# DCDC-TPS54361QDPRRQ1.net
KiCad netlist of a schematic drawn in Altium Designer
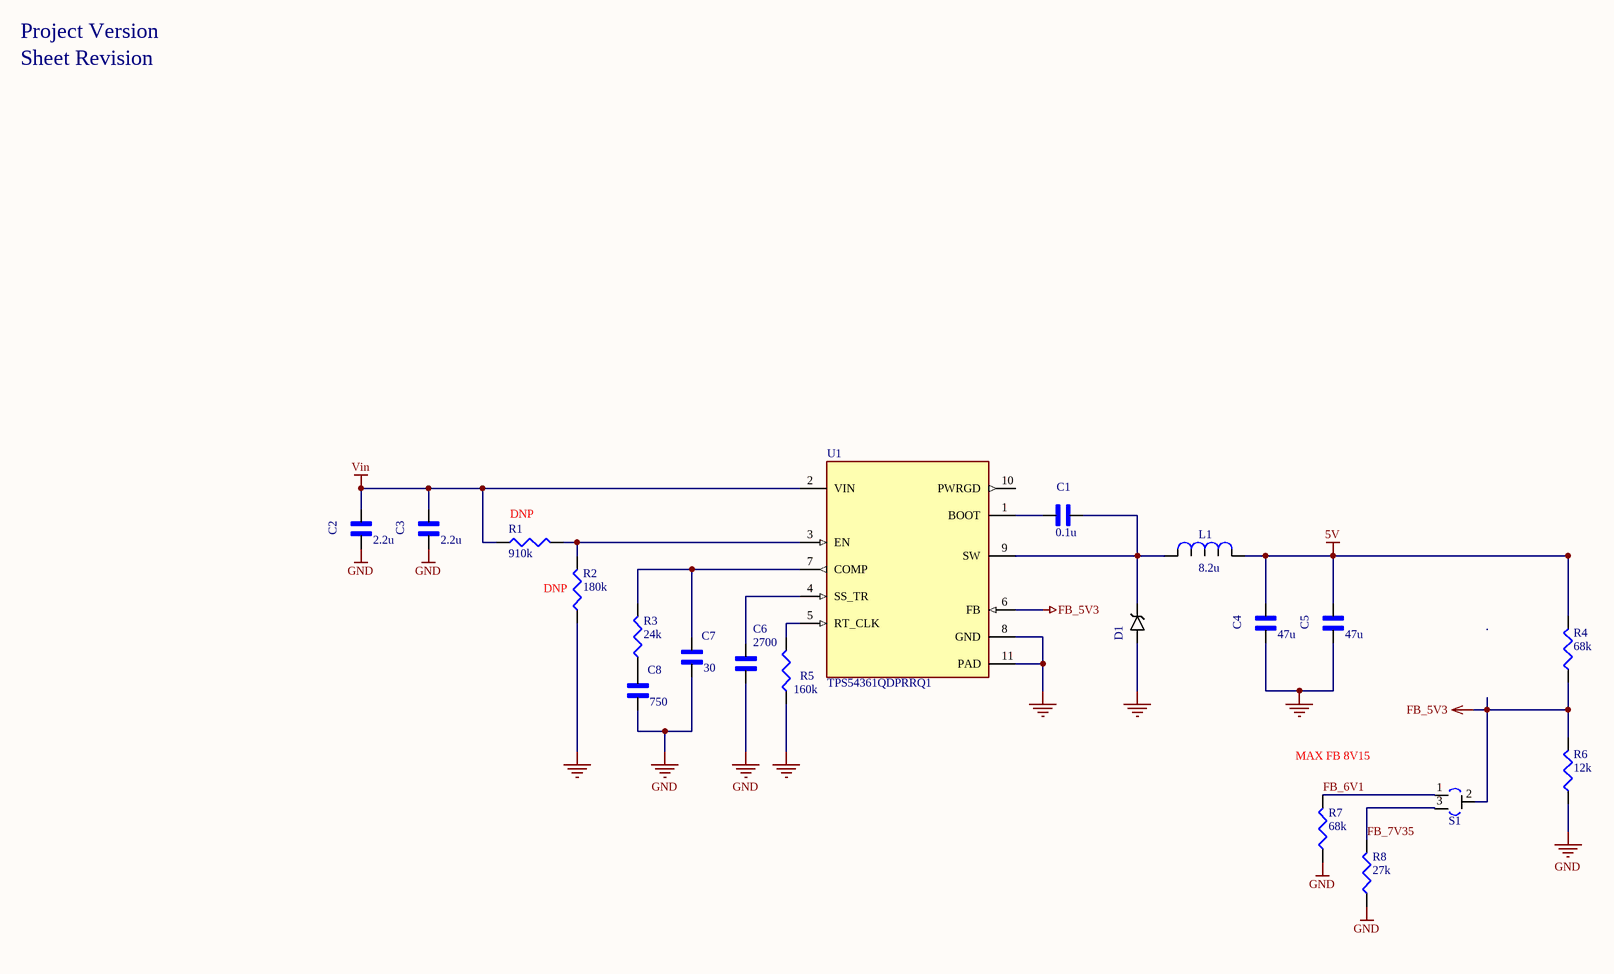
[diagram p0: DCDC-TPS54361QDPRRQ1.SchDoc]

(export (version "E")
  (design (tool "Eeschema 10.0.6"))
  (components
    (comp (ref "C1")
      (value "0.1u")
      (footprint "*CAPC1608X90")
      (description "Cap Thin Film 0.1uf 50v 0603")
      (fields (field (name "MF") "AVX") (field (name "MP") "GX035C104MAT2-500"))
      (libsource (lib "lib") (part "GX035C104MAT2-500"))
    )
    (comp (ref "C2")
      (value "2.2u")
      (footprint "*CAP3216X125N")
      (description "1206 2.2 uF 50 V В±10% Tolerance X7R SMT Multilayer Ceramic Capacitor")
      (fields (field (name "MF") "Murata Electronics") (field (name "MP") "GRM31CR71H225KA88L"))
      (libsource (lib "lib") (part "GRM31CR71H225KA88L"))
    )
    (comp (ref "C3")
      (value "2.2u")
      (footprint "*CAP3216X125N")
      (description "1206 2.2 uF 50 V В±10% Tolerance X7R SMT Multilayer Ceramic Capacitor")
      (fields (field (name "MF") "Murata Electronics") (field (name "MP") "GRM31CR71H225KA88L"))
      (libsource (lib "lib") (part "GRM31CR71H225KA88L"))
    )
    (comp (ref "C4")
      (value "47u")
      (footprint "*CAPC3216X125N")
      (description "Multilayer Ceramic Capacitor, GRM Series, 47 - F, - 10%, X5R, 10 V, 1206 [3216 Metric]")
      (fields (field (name "MF") "Murata Electronics") (field (name "MP") "GRM31CR61A476KE15L"))
      (libsource (lib "lib") (part "GRM31CR61A476KE15L"))
    )
    (comp (ref "C5")
      (value "47u")
      (footprint "*CAPC3216X125N")
      (description "Multilayer Ceramic Capacitor, GRM Series, 47 - F, - 10%, X5R, 10 V, 1206 [3216 Metric]")
      (fields (field (name "MF") "Murata Electronics") (field (name "MP") "GRM31CR61A476KE15L"))
      (libsource (lib "lib") (part "GRM31CR61A476KE15L"))
    )
    (comp (ref "C6")
      (value "2700")
      (footprint "CAP0603")
      (description "Конденсатор 0603 2700 пФ 50В Конденсатор керамический")
      (fields (field (name "MP") "GRM188R71H272KA01D"))
      (libsource (lib "Lib_AB") (part "GRM188R71H272KA01D"))
    )
    (comp (ref "C7")
      (value "30")
      (footprint "CAP0603")
      (description "Конденсатор 0603 30пФ 50В Конденсатор керамический smd 30 пФ 0603")
      (fields (field (name "MP") "MLCC30pFNPO50V5%0603"))
      (libsource (lib "Lib_AB") (part "MLCC30pFNPO50V5%0603"))
    )
    (comp (ref "C8")
      (value "750")
      (footprint "CAP0603")
      (description "Конденсатор 0603 750 пФ 50В Конденсатор керамический")
      (fields (field (name "MP") "GRM1885C1H751JA01D"))
      (libsource (lib "Lib_AB") (part "GRM1885C1H751JA01D"))
    )
    (comp (ref "D1")
      (value "SK56")
      (footprint "*SMB_P6SMB62AT3G(Primary)")
      (description "Диод Шоттки 5А 60В [SMB / DO-214AA]")
      (fields (field (name "MF") "Littelfuse Inc."))
      (libsource (lib "lib") (part "SK56"))
    )
    (comp (ref "L1")
      (value "8.2u")
      (footprint "*IND_IHLP_2525_CZ")
      (description "IHLP2525CZER8R2M01, 8.2uH 4A 20% Low Profile High Current SMT Inductor, Индуктивность")
      (fields (field (name "MP") "IHLP2525CZER8R2M01") (field (name "MF") "Vishay Dale"))
      (libsource (lib "lib") (part "IHLP2525CZER8R2M01"))
    )
    (comp (ref "R1")
      (value "910k")
      (footprint "J1-0603")
      (description "910 kOhms ±1% 0.1W, 1/10W Chip Resistor 0603 (1608 Metric) Moisture Resistant Thick Film")
      (fields
        (field (name "INSTRUCTIONS") "DNP")
        (field (name "MF") "Yageo or NXP")
        (field (name "MP") "RC0603FR-07910KL")
      )
      (libsource (lib "lib") (part "RC0603FR-07910KL"))
    )
    (comp (ref "R2")
      (value "180k")
      (footprint "J1-0603")
      (description "180 kOhms ±1% 0.1W, 1/10W Chip Resistor 0603 (1608 Metric) Moisture Resistant Thick Film")
      (fields
        (field (name "INSTRUCTIONS") "DNP")
        (field (name "MF") "Yageo or NXP")
        (field (name "MP") "RC0603FR-07180KL")
      )
      (libsource (lib "lib") (part "RC0603FR-07180KL"))
    )
    (comp (ref "R3")
      (value "24k")
      (footprint "J1-0603")
      (description "Резистор 0603  24 kOhms ±1% 0.1W, 1/10W Chip Resistor 0603 (1608 Metric) Thick Film")
      (fields (field (name "MF") "Yageo or NXP") (field (name "MP") "RC0603FR-0724KL"))
      (libsource (lib "Lib_AB") (part "RC0603FR-0724KL"))
    )
    (comp (ref "R4")
      (value "68k")
      (footprint "J1-0603")
      (fields
        (field (name "MF") "Yageo or NXP")
        (field (name "MP") "RC0603FR-0768KL")
        (field (name "Comment") "RC0603FR-0762KL")
      )
      (libsource (lib "Lib_AB") (part "RC0603FR-0768KL"))
    )
    (comp (ref "R5")
      (value "160k")
      (footprint "J1-0603")
      (description "160 kOhms ±1% 0.1W, 1/10W Chip Resistor 0603 (1608 Metric) Moisture Resistant Thick Film")
      (fields (field (name "MF") "Yageo or NXP") (field (name "MP") "RC0603FR-07160KL"))
      (libsource (lib "lib") (part "RC0603FR-07160KL"))
    )
    (comp (ref "R6")
      (value "12k")
      (footprint "J1-0603")
      (description "Resistor")
      (fields (field (name "MP") "4.7K 1% 0603") (field (name "Comment") "Res3"))
      (libsource (lib "Miscellaneous Devices") (part "Res3"))
    )
    (comp (ref "R7")
      (value "68k")
      (footprint "J1-0603")
      (fields
        (field (name "MF") "Yageo or NXP")
        (field (name "MP") "RC0603FR-0768KL")
        (field (name "Comment") "RC0603FR-0762KL")
      )
      (libsource (lib "Lib_AB") (part "RC0603FR-0768KL"))
    )
    (comp (ref "R8")
      (value "27k")
      (footprint "J1-0603")
      (description "Резистор 0603  27 kOhms ±1% 0.1W, 1/10W Chip Resistor 0603 (1608 Metric) Thick Film")
      (fields (field (name "MF") "Yageo or NXP") (field (name "MP") "RC0603FR-0727KL"))
      (libsource (lib "Lib_AB") (part "RC0603FR-0727KL"))
    )
    (comp (ref "S1") (value "selector") (footprint "SELECTOR") (libsource (lib "lib") (part "selector")))
    (comp (ref "U1")
      (value "TPS54361QDPRRQ1")
      (footprint "DPR0010A")
      (description "4.5-V to 60-V Input, 3.5-A, Step Down DC-DC Converter with Soft-Start 10-WSON -40 to 125")
      (fields (field (name "MF") "Texas Instruments"))
      (libsource (lib "Lib_AB") (part "TPS54361QDPRRQ1"))
    )
  )
  (nets
    (net (code "1") (name "/FB_6V1") (class "Default")
      (node (ref "R7") (pin "2") (pinfunction "2_2") (pintype "passive"))
      (node (ref "S1") (pin "1") (pinfunction "IN1_1") (pintype "passive"))
    )
    (net (code "2") (name "/FB_7V35") (class "Default")
      (node (ref "R8") (pin "2") (pinfunction "2_2") (pintype "passive"))
      (node (ref "S1") (pin "3") (pinfunction "IN3_3") (pintype "passive"))
    )
    (net (code "3") (name "5V") (class "Default")
      (node (ref "C4") (pin "2") (pinfunction "2_2") (pintype "passive"))
      (node (ref "C5") (pin "2") (pinfunction "2_2") (pintype "passive"))
      (node (ref "L1") (pin "1") (pinfunction "1_1") (pintype "passive"))
      (node (ref "R4") (pin "2") (pinfunction "2_2") (pintype "passive"))
    )
    (net (code "4") (name "FB_5V3") (class "Default")
      (node (ref "R4") (pin "1") (pinfunction "1_1") (pintype "passive"))
      (node (ref "R6") (pin "2") (pinfunction "2_2") (pintype "passive"))
      (node (ref "S1") (pin "2") (pinfunction "MID_2") (pintype "passive"))
      (node (ref "U1") (pin "6") (pinfunction "FB_6") (pintype "input"))
    )
    (net (code "5") (name "GND") (class "Default")
      (node (ref "C2") (pin "2") (pinfunction "2_2") (pintype "passive"))
      (node (ref "C3") (pin "2") (pinfunction "2_2") (pintype "passive"))
      (node (ref "C4") (pin "1") (pinfunction "1_1") (pintype "passive"))
      (node (ref "C5") (pin "1") (pinfunction "1_1") (pintype "passive"))
      (node (ref "C6") (pin "1") (pinfunction "1_1") (pintype "passive"))
      (node (ref "C7") (pin "1") (pinfunction "1_1") (pintype "passive"))
      (node (ref "C8") (pin "1") (pinfunction "1_1") (pintype "passive"))
      (node (ref "D1") (pin "A") (pinfunction "A_A") (pintype "power_in"))
      (node (ref "R2") (pin "1") (pinfunction "1_1") (pintype "passive"))
      (node (ref "R5") (pin "1") (pinfunction "1_1") (pintype "passive"))
      (node (ref "R6") (pin "1") (pinfunction "1_1") (pintype "passive"))
      (node (ref "R7") (pin "1") (pinfunction "1_1") (pintype "passive"))
      (node (ref "R8") (pin "1") (pinfunction "1_1") (pintype "passive"))
      (node (ref "U1") (pin "11") (pinfunction "PAD_11") (pintype "passive"))
      (node (ref "U1") (pin "8") (pinfunction "GND_8") (pintype "power_in"))
    )
    (net (code "6") (name "Net-(C8-Pad2)") (class "Default")
      (node (ref "C8") (pin "2") (pinfunction "2_2") (pintype "passive"))
      (node (ref "R3") (pin "1") (pinfunction "1_1") (pintype "passive"))
    )
    (net (code "7") (name "Net-(U1-BOOT)") (class "Default")
      (node (ref "C1") (pin "2") (pinfunction "2_2") (pintype "passive"))
      (node (ref "U1") (pin "1") (pinfunction "BOOT_1") (pintype "power_in"))
    )
    (net (code "8") (name "Net-(U1-COMP)") (class "Default")
      (node (ref "C7") (pin "2") (pinfunction "2_2") (pintype "passive"))
      (node (ref "R3") (pin "2") (pinfunction "2_2") (pintype "passive"))
      (node (ref "U1") (pin "7") (pinfunction "COMP_7") (pintype "output"))
    )
    (net (code "9") (name "Net-(U1-EN)") (class "Default")
      (node (ref "R1") (pin "2") (pinfunction "2_2") (pintype "passive"))
      (node (ref "R2") (pin "2") (pinfunction "2_2") (pintype "passive"))
      (node (ref "U1") (pin "3") (pinfunction "EN_3") (pintype "input"))
    )
    (net (code "10") (name "Net-(U1-RT_CLK)") (class "Default")
      (node (ref "R5") (pin "2") (pinfunction "2_2") (pintype "passive"))
      (node (ref "U1") (pin "5") (pinfunction "RT_CLK_5") (pintype "input"))
    )
    (net (code "11") (name "Net-(U1-SS_TR)") (class "Default")
      (node (ref "C6") (pin "2") (pinfunction "2_2") (pintype "passive"))
      (node (ref "U1") (pin "4") (pinfunction "SS_TR_4") (pintype "input"))
    )
    (net (code "12") (name "Net-(U1-SW)") (class "Default")
      (node (ref "C1") (pin "1") (pinfunction "1_1") (pintype "passive"))
      (node (ref "D1") (pin "C") (pinfunction "C_C") (pintype "power_in"))
      (node (ref "L1") (pin "2") (pinfunction "2_2") (pintype "passive"))
      (node (ref "U1") (pin "9") (pinfunction "SW_9") (pintype "power_in"))
    )
    (net (code "13") (name "Vin") (class "Default")
      (node (ref "C2") (pin "1") (pinfunction "1_1") (pintype "passive"))
      (node (ref "C3") (pin "1") (pinfunction "1_1") (pintype "passive"))
      (node (ref "R1") (pin "1") (pinfunction "1_1") (pintype "passive"))
      (node (ref "U1") (pin "2") (pinfunction "VIN_2") (pintype "power_in"))
    )
    (net (code "14") (name "unconnected-(U1-PWRGD-Pad10)") (class "Default")
      (node (ref "U1") (pin "10") (pinfunction "PWRGD_10") (pintype "output"))
    )
  )
)
